# esquematico_placa.net
KiCad netlist of a schematic drawn in EAGLE
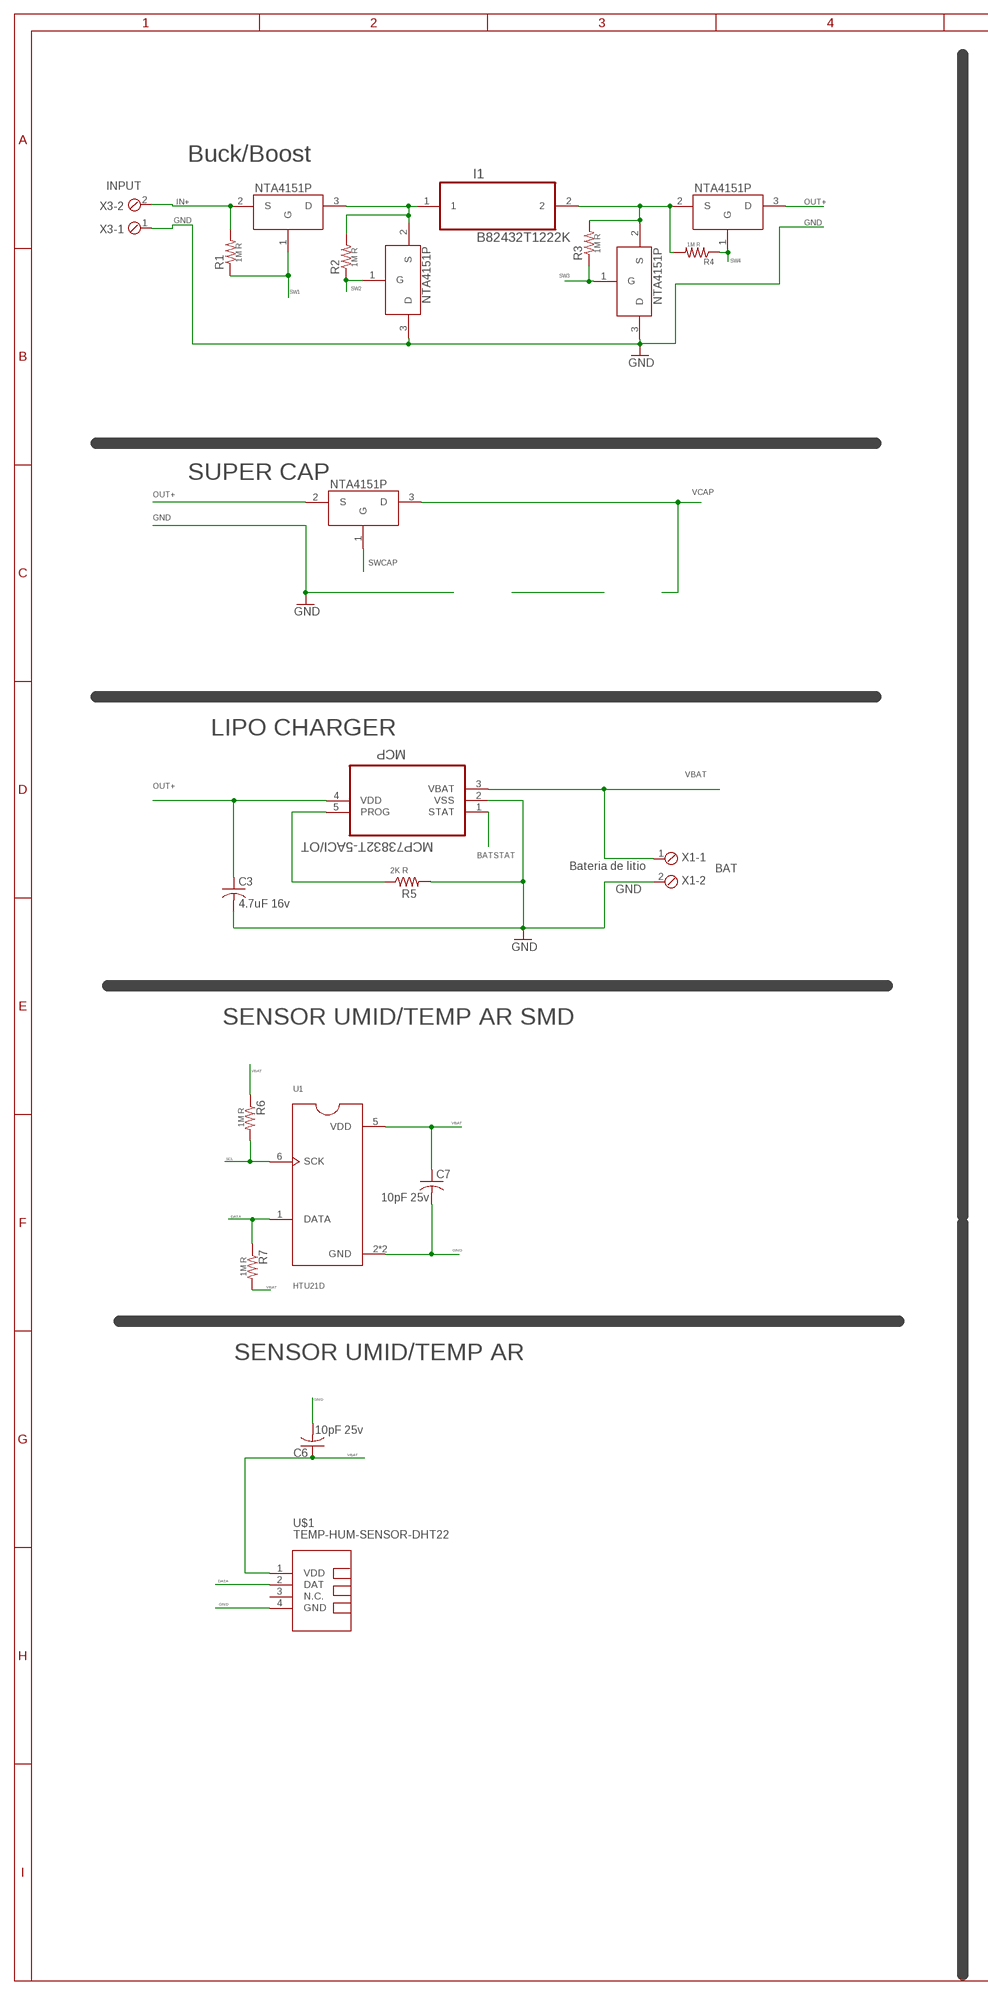
[diagram p0: schematic, sheet 1, part 1 of 2]
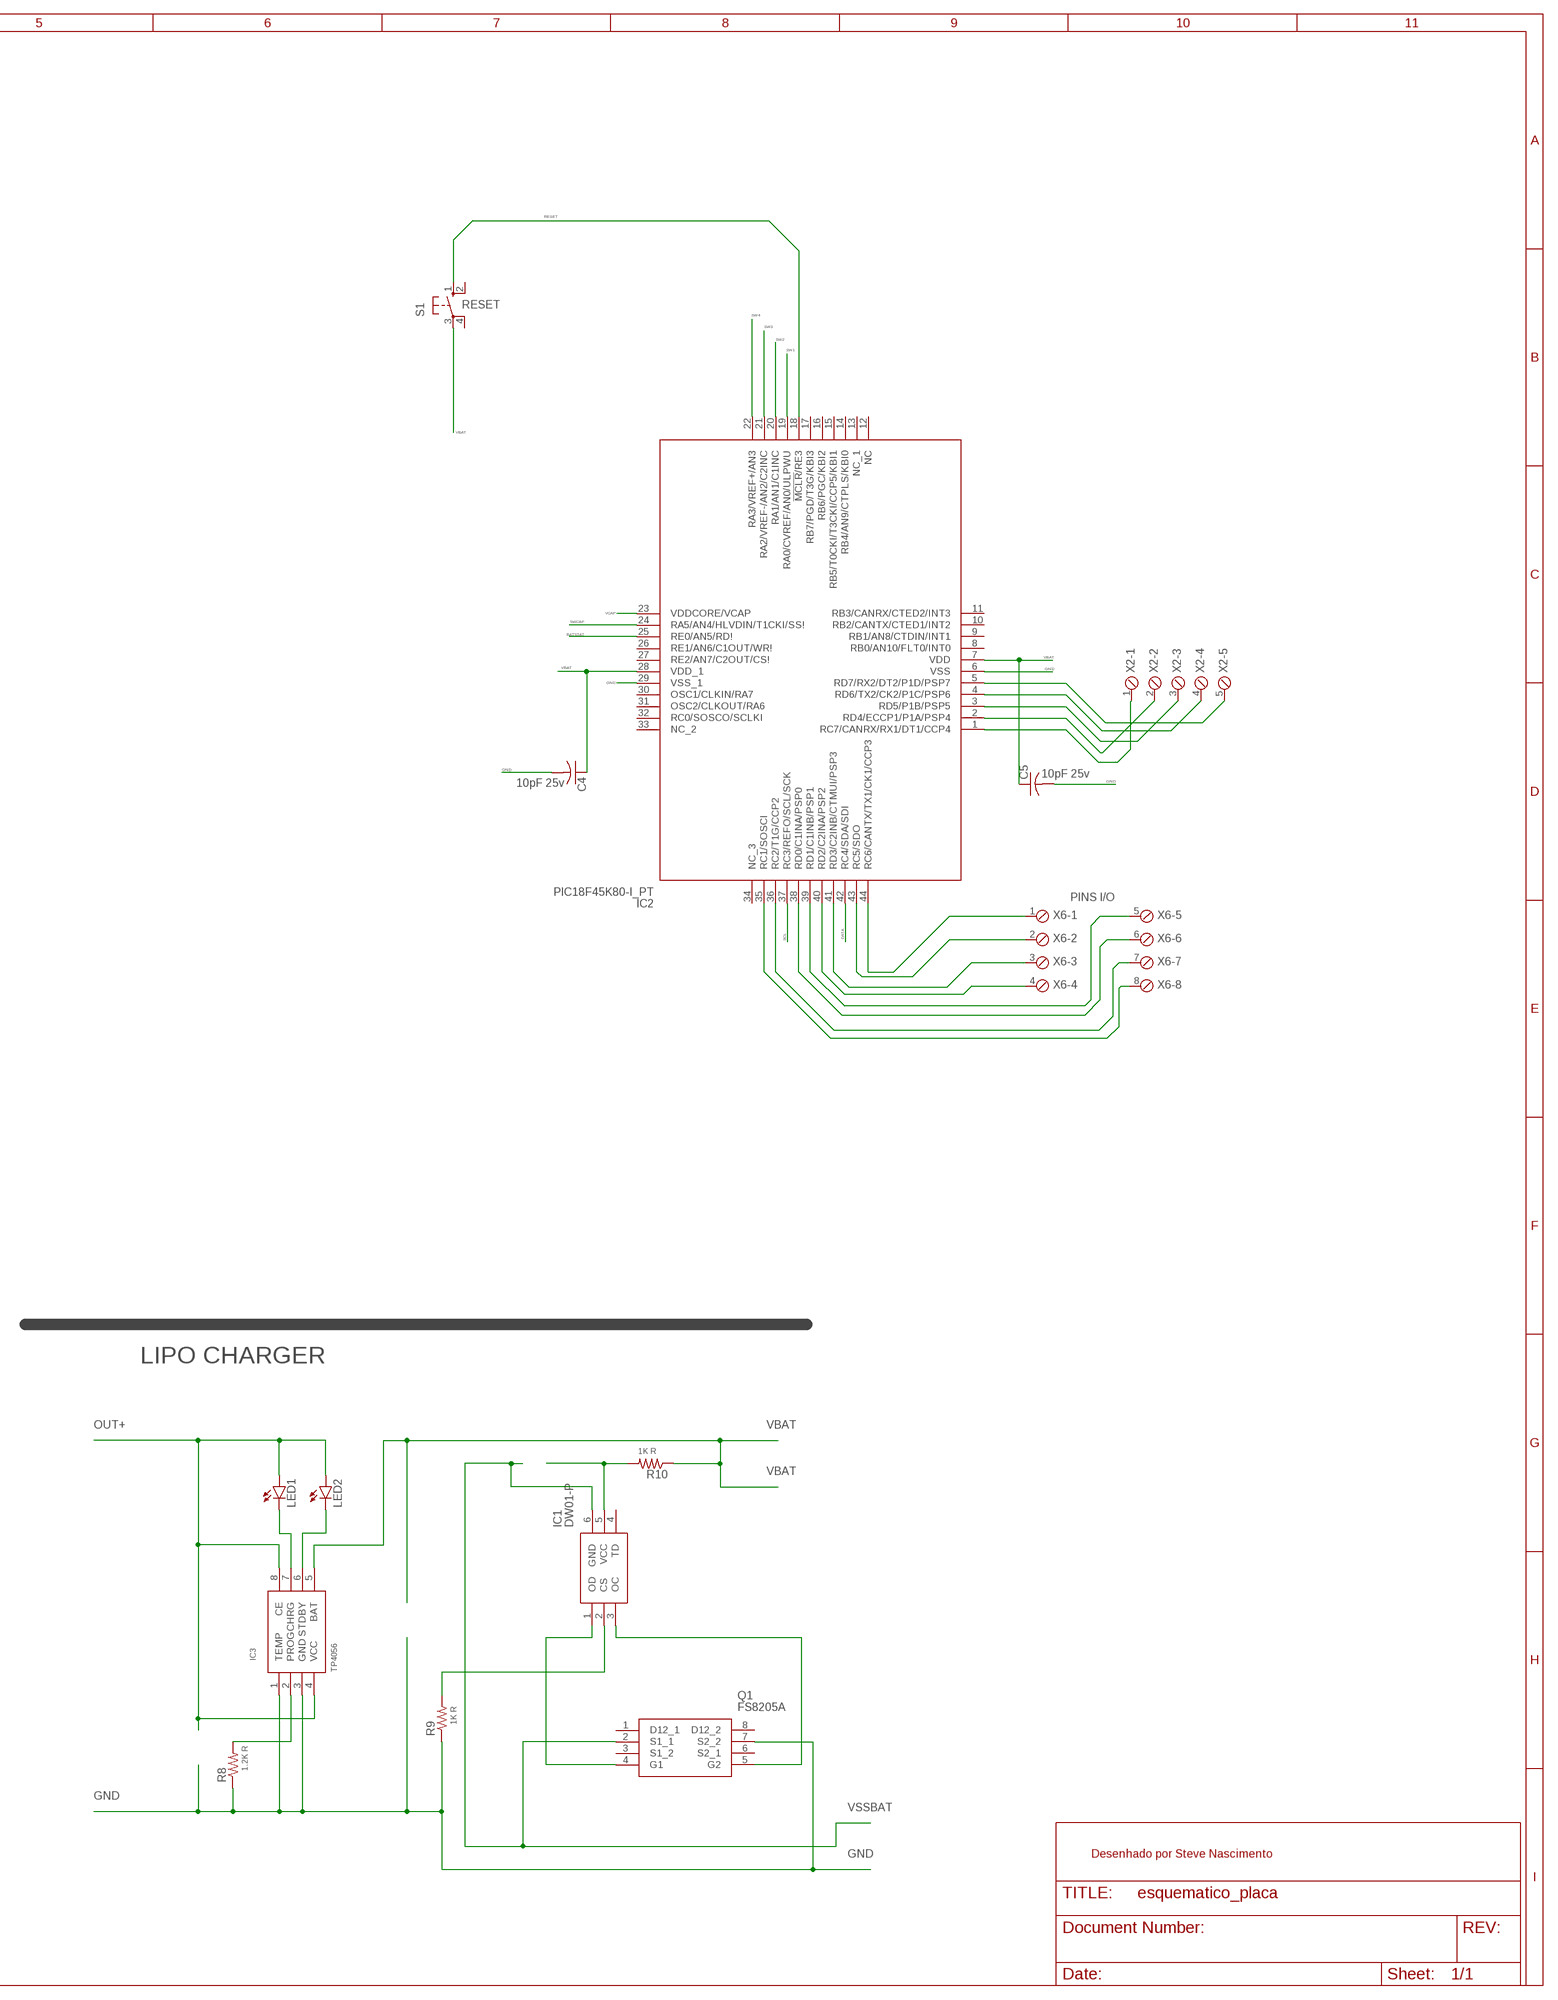
[diagram p1: schematic, sheet 1, part 2 of 2]

(export (version "E")
  (design (tool "Eeschema 10.0.6"))
  (components
    (comp (ref "C3")
      (value "4.7uF 16v")
      (footprint "eagle-import:C0805")
      (libsource (lib "eagle-import") (part "C-USC0805"))
    )
    (comp (ref "C4")
      (value "10pF 25v")
      (footprint "eagle-import:C0805")
      (libsource (lib "eagle-import") (part "C-USC0805"))
    )
    (comp (ref "C5")
      (value "10pF 25v")
      (footprint "eagle-import:C0805")
      (libsource (lib "eagle-import") (part "C-USC0805"))
    )
    (comp (ref "C6")
      (value "10pF 25v")
      (footprint "eagle-import:C0805")
      (libsource (lib "eagle-import") (part "C-USC0805"))
    )
    (comp (ref "C7")
      (value "10pF 25v")
      (footprint "eagle-import:C0805")
      (libsource (lib "eagle-import") (part "C-USC0805"))
    )
    (comp (ref "I1")
      (value "B82432T1222K")
      (footprint "eagle-import:INDC4532X340N")
      (fields (field (name "MF") "EPCOS"))
      (libsource (lib "eagle-import") (part "B82432T1222K"))
    )
    (comp (ref "IC1")
      (value "DW01-P")
      (footprint "eagle-import:SOT95P280X135-6N")
      (libsource (lib "eagle-import") (part "DW01-P"))
    )
    (comp (ref "IC2")
      (value "PIC18F45K80-I_PT")
      (footprint "eagle-import:QFP80P1200X1200X120-44N")
      (fields
        (field (name "MANUFACTURER_PART_NUMBER") "PIC18F45K80-I/PT")
        (field (name "MOUSER_PART_NUMBER") "579-PIC18F45K80-I/PT")
        (field (name "RS_PART_NUMBER") "8895477")
      )
      (libsource (lib "eagle-import") (part "PIC18F45K80-I_PT"))
    )
    (comp (ref "IC3")
      (value "TP4056")
      (footprint "eagle-import:SOP-8")
      (libsource (lib "eagle-import") (part "TP4056"))
    )
    (comp (ref "LED1")
      (value "LED5MM")
      (footprint "eagle-import:LED5MM")
      (libsource (lib "eagle-import") (part "LED5MM"))
    )
    (comp (ref "LED2")
      (value "LED5MM")
      (footprint "eagle-import:LED5MM")
      (libsource (lib "eagle-import") (part "LED5MM"))
    )
    (comp (ref "M1")
      (value "NTA4151P")
      (footprint "eagle-import:SOT50P160X90-3N")
      (libsource (lib "eagle-import") (part "NTA4151P"))
    )
    (comp (ref "M2")
      (value "NTA4151P")
      (footprint "eagle-import:SOT50P160X90-3N")
      (libsource (lib "eagle-import") (part "NTA4151P"))
    )
    (comp (ref "M3")
      (value "NTA4151P")
      (footprint "eagle-import:SOT50P160X90-3N")
      (libsource (lib "eagle-import") (part "NTA4151P"))
    )
    (comp (ref "M4")
      (value "NTA4151P")
      (footprint "eagle-import:SOT50P160X90-3N")
      (libsource (lib "eagle-import") (part "NTA4151P"))
    )
    (comp (ref "MCP")
      (value "MCP73832T-5ACI/OT")
      (footprint "eagle-import:SOT95P300X145-5N")
      (fields (field (name "MF") "Microchip"))
      (libsource (lib "eagle-import") (part "MCP73832T-5ACI/OT"))
    )
    (comp (ref "Q1")
      (value "FS8205A")
      (footprint "eagle-import:SOP65P640X120-8N")
      (libsource (lib "eagle-import") (part "FS8205A"))
    )
    (comp (ref "R1")
      (value "1M R")
      (footprint "eagle-import:RESC2012X65N")
      (fields
        (field (name "COMMENT") "5-1879509-5")
        (field (name "MF") "TE Connectivity")
        (field (name "MP") "CRGH0805F392R")
      )
      (libsource (lib "eagle-import") (part "CRGH0805F392R"))
    )
    (comp (ref "R2")
      (value "1M R")
      (footprint "eagle-import:RESC2012X65N")
      (fields
        (field (name "COMMENT") "5-1879509-5")
        (field (name "MF") "TE Connectivity")
        (field (name "MP") "CRGH0805F392R")
      )
      (libsource (lib "eagle-import") (part "CRGH0805F392R"))
    )
    (comp (ref "R3")
      (value "1M R")
      (footprint "eagle-import:RESC2012X65N")
      (fields
        (field (name "COMMENT") "5-1879509-5")
        (field (name "MF") "TE Connectivity")
        (field (name "MP") "CRGH0805F392R")
      )
      (libsource (lib "eagle-import") (part "CRGH0805F392R"))
    )
    (comp (ref "R4")
      (value "1M R")
      (footprint "eagle-import:RESC2012X65N")
      (fields
        (field (name "COMMENT") "5-1879509-5")
        (field (name "MF") "TE Connectivity")
        (field (name "MP") "CRGH0805F392R")
      )
      (libsource (lib "eagle-import") (part "CRGH0805F392R"))
    )
    (comp (ref "R5")
      (value "2K R")
      (footprint "eagle-import:RESC2012X65N")
      (fields
        (field (name "COMMENT") "5-1879509-5")
        (field (name "MF") "TE Connectivity")
        (field (name "MP") "CRGH0805F392R")
      )
      (libsource (lib "eagle-import") (part "CRGH0805F392R"))
    )
    (comp (ref "R6")
      (value "1M R")
      (footprint "eagle-import:RESC2012X65N")
      (fields
        (field (name "COMMENT") "5-1879509-5")
        (field (name "MF") "TE Connectivity")
        (field (name "MP") "CRGH0805F392R")
      )
      (libsource (lib "eagle-import") (part "CRGH0805F392R"))
    )
    (comp (ref "R7")
      (value "1M R")
      (footprint "eagle-import:RESC2012X65N")
      (fields
        (field (name "COMMENT") "5-1879509-5")
        (field (name "MF") "TE Connectivity")
        (field (name "MP") "CRGH0805F392R")
      )
      (libsource (lib "eagle-import") (part "CRGH0805F392R"))
    )
    (comp (ref "R8")
      (value "1.2K R")
      (footprint "eagle-import:RESC2012X65N")
      (fields
        (field (name "COMMENT") "5-1879509-5")
        (field (name "MF") "TE Connectivity")
        (field (name "MP") "CRGH0805F392R")
      )
      (libsource (lib "eagle-import") (part "CRGH0805F392R"))
    )
    (comp (ref "R9")
      (value "1K R")
      (footprint "eagle-import:RESC2012X65N")
      (fields
        (field (name "COMMENT") "5-1879509-5")
        (field (name "MF") "TE Connectivity")
        (field (name "MP") "CRGH0805F392R")
      )
      (libsource (lib "eagle-import") (part "CRGH0805F392R"))
    )
    (comp (ref "R10")
      (value "1K R")
      (footprint "eagle-import:RESC2012X65N")
      (fields
        (field (name "COMMENT") "5-1879509-5")
        (field (name "MF") "TE Connectivity")
        (field (name "MP") "CRGH0805F392R")
      )
      (libsource (lib "eagle-import") (part "CRGH0805F392R"))
    )
    (comp (ref "S1")
      (value "RESET")
      (footprint "eagle-import:B3F-10XX")
      (fields (field (name "MPN") "B3F-1000"))
      (libsource (lib "eagle-import") (part "10-XX"))
    )
    (comp (ref "SC")
      (value "NTA4151P")
      (footprint "eagle-import:SOT50P160X90-3N")
      (libsource (lib "eagle-import") (part "NTA4151P"))
    )
    (comp (ref "U$1")
      (value "TEMP-HUM-SENSOR-DHT22")
      (footprint "eagle-import:TEMP-HUM-SENSOR-DHT22")
      (libsource (lib "eagle-import") (part "TEMP-HUM-SENSOR-DHT22"))
    )
    (comp (ref "U1")
      (value "HTU21D")
      (footprint "eagle-import:QFN100P300X300X100-7N")
      (fields (field (name "COMMENT") "CAT-HSC0004") (field (name "MF") "TE Connectivity"))
      (libsource (lib "eagle-import") (part "HTU21D"))
    )
    (comp (ref "X1")
      (value "BAT")
      (footprint "eagle-import:2POL254")
      (libsource (lib "eagle-import") (part "MPT2"))
    )
    (comp (ref "X2")
      (value "MPT5")
      (footprint "eagle-import:5POL254")
      (libsource (lib "eagle-import") (part "MPT5"))
    )
    (comp (ref "X3")
      (value "INPUT")
      (footprint "eagle-import:2POL254")
      (libsource (lib "eagle-import") (part "MPT2"))
    )
    (comp (ref "X6")
      (value "PINS I/O")
      (footprint "eagle-import:8POL254")
      (libsource (lib "eagle-import") (part "MPT8"))
    )
  )
  (nets
    (net (code "1") (name "/BATSTAT") (class "Default")
      (node (ref "IC2") (pin "25") (pinfunction "RE0/AN5/RD~{}_25") (pintype "bidirectional"))
      (node (ref "MCP") (pin "1") (pinfunction "STAT_1") (pintype "input"))
    )
    (net (code "2") (name "/DATA") (class "Default")
      (node (ref "IC2") (pin "42") (pinfunction "RC4/SDA/SDI_42") (pintype "bidirectional"))
      (node (ref "R7") (pin "1") (pinfunction "1_1") (pintype "passive"))
      (node (ref "U$1") (pin "2") (pinfunction "DAT_2") (pintype "bidirectional"))
      (node (ref "U1") (pin "1") (pinfunction "DATA_1") (pintype "bidirectional"))
    )
    (net (code "3") (name "/IN+") (class "Default")
      (node (ref "M1") (pin "2") (pinfunction "S_2") (pintype "bidirectional"))
      (node (ref "R1") (pin "2") (pinfunction "2_2") (pintype "passive"))
      (node (ref "X3") (pin "2") (pinfunction "1_2") (pintype "passive"))
    )
    (net (code "4") (name "/OUT+") (class "Default")
      (node (ref "C3") (pin "1") (pinfunction "1_1") (pintype "passive"))
      (node (ref "IC3") (pin "4") (pinfunction "VCC_4") (pintype "bidirectional"))
      (node (ref "IC3") (pin "8") (pinfunction "CE_8") (pintype "bidirectional"))
      (node (ref "LED1") (pin "A") (pinfunction "A_A") (pintype "passive"))
      (node (ref "LED2") (pin "A") (pinfunction "A_A") (pintype "passive"))
      (node (ref "M4") (pin "3") (pinfunction "D_3") (pintype "bidirectional"))
      (node (ref "MCP") (pin "4") (pinfunction "VDD_4") (pintype "power_in"))
      (node (ref "SC") (pin "2") (pinfunction "S_2") (pintype "bidirectional"))
    )
    (net (code "5") (name "/RESET") (class "Default")
      (node (ref "IC2") (pin "18") (pinfunction "~{MCLR}/RE3_18") (pintype "bidirectional"))
      (node (ref "S1") (pin "1") (pinfunction "S_1") (pintype "passive"))
    )
    (net (code "6") (name "/SCL") (class "Default")
      (node (ref "IC2") (pin "37") (pinfunction "RC3/REFO/SCL/SCK_37") (pintype "input"))
      (node (ref "R6") (pin "2") (pinfunction "2_2") (pintype "passive"))
      (node (ref "U1") (pin "6") (pinfunction "SCK_6") (pintype "input"))
    )
    (net (code "7") (name "/SW1") (class "Default")
      (node (ref "IC2") (pin "19") (pinfunction "RA0/CVREF/AN0/ULPWU_19") (pintype "input"))
      (node (ref "M1") (pin "1") (pinfunction "G_1") (pintype "bidirectional"))
      (node (ref "R1") (pin "1") (pinfunction "1_1") (pintype "passive"))
    )
    (net (code "8") (name "/SW2") (class "Default")
      (node (ref "IC2") (pin "20") (pinfunction "RA1/AN1/C1INC_20") (pintype "input"))
      (node (ref "M2") (pin "1") (pinfunction "G_1") (pintype "bidirectional"))
      (node (ref "R2") (pin "1") (pinfunction "1_1") (pintype "passive"))
    )
    (net (code "9") (name "/SW3") (class "Default")
      (node (ref "IC2") (pin "21") (pinfunction "RA2/VREF-/AN2/C2INC_21") (pintype "input"))
      (node (ref "M3") (pin "1") (pinfunction "G_1") (pintype "bidirectional"))
      (node (ref "R3") (pin "1") (pinfunction "1_1") (pintype "passive"))
    )
    (net (code "10") (name "/SW4") (class "Default")
      (node (ref "IC2") (pin "22") (pinfunction "RA3/VREF+/AN3_22") (pintype "input"))
      (node (ref "M4") (pin "1") (pinfunction "G_1") (pintype "bidirectional"))
      (node (ref "R4") (pin "1") (pinfunction "1_1") (pintype "passive"))
    )
    (net (code "11") (name "/SWCAP") (class "Default")
      (node (ref "IC2") (pin "24") (pinfunction "RA5/AN4/HLVDIN/T1CKI/SS~{}_24") (pintype "input"))
      (node (ref "SC") (pin "1") (pinfunction "G_1") (pintype "bidirectional"))
    )
    (net (code "12") (name "/VBAT") (class "Default")
      (node (ref "C4") (pin "1") (pinfunction "1_1") (pintype "passive"))
      (node (ref "C5") (pin "1") (pinfunction "1_1") (pintype "passive"))
      (node (ref "C6") (pin "1") (pinfunction "1_1") (pintype "passive"))
      (node (ref "C7") (pin "1") (pinfunction "1_1") (pintype "passive"))
      (node (ref "IC2") (pin "28") (pinfunction "VDD_1_28") (pintype "power_in"))
      (node (ref "IC2") (pin "7") (pinfunction "VDD_7") (pintype "power_in"))
      (node (ref "IC3") (pin "5") (pinfunction "BAT_5") (pintype "bidirectional"))
      (node (ref "MCP") (pin "3") (pinfunction "VBAT_3") (pintype "input"))
      (node (ref "R10") (pin "1") (pinfunction "1_1") (pintype "passive"))
      (node (ref "R6") (pin "1") (pinfunction "1_1") (pintype "passive"))
      (node (ref "R7") (pin "2") (pinfunction "2_2") (pintype "passive"))
      (node (ref "S1") (pin "3") (pinfunction "P_3") (pintype "passive"))
      (node (ref "U$1") (pin "1") (pinfunction "VDD_1") (pintype "power_in"))
      (node (ref "U1") (pin "5") (pinfunction "VDD_5") (pintype "power_in"))
      (node (ref "X1") (pin "1") (pinfunction "1_1") (pintype "passive"))
    )
    (net (code "13") (name "/VCAP") (class "Default")
      (node (ref "IC2") (pin "23") (pinfunction "VDDCORE/VCAP_23") (pintype "power_in"))
      (node (ref "SC") (pin "3") (pinfunction "D_3") (pintype "bidirectional"))
    )
    (net (code "14") (name "/VSSBAT") (class "Default")
      (node (ref "IC1") (pin "6") (pinfunction "GND_6") (pintype "bidirectional"))
      (node (ref "Q1") (pin "2") (pinfunction "S1_1_2") (pintype "bidirectional"))
    )
    (net (code "15") (name "GND") (class "Default")
      (node (ref "C3") (pin "2") (pinfunction "2_2") (pintype "passive"))
      (node (ref "C4") (pin "2") (pinfunction "2_2") (pintype "passive"))
      (node (ref "C5") (pin "2") (pinfunction "2_2") (pintype "passive"))
      (node (ref "C6") (pin "2") (pinfunction "2_2") (pintype "passive"))
      (node (ref "C7") (pin "2") (pinfunction "2_2") (pintype "passive"))
      (node (ref "IC2") (pin "29") (pinfunction "VSS_1_29") (pintype "power_in"))
      (node (ref "IC2") (pin "6") (pinfunction "VSS_6") (pintype "power_in"))
      (node (ref "IC3") (pin "1") (pinfunction "TEMP_1") (pintype "bidirectional"))
      (node (ref "IC3") (pin "3") (pinfunction "GND_3") (pintype "bidirectional"))
      (node (ref "M2") (pin "3") (pinfunction "D_3") (pintype "bidirectional"))
      (node (ref "M3") (pin "3") (pinfunction "D_3") (pintype "bidirectional"))
      (node (ref "MCP") (pin "2") (pinfunction "VSS_2") (pintype "passive"))
      (node (ref "Q1") (pin "7") (pinfunction "S2_2_7") (pintype "bidirectional"))
      (node (ref "R5") (pin "2") (pinfunction "2_2") (pintype "passive"))
      (node (ref "R8") (pin "1") (pinfunction "1_1") (pintype "passive"))
      (node (ref "R9") (pin "1") (pinfunction "1_1") (pintype "passive"))
      (node (ref "U$1") (pin "4") (pinfunction "GND_4") (pintype "power_in"))
      (node (ref "U1") (pin "2") (pinfunction "GND_2") (pintype "passive"))
      (node (ref "U1") (pin "PAD") (pinfunction "GND_PAD") (pintype "passive"))
      (node (ref "X1") (pin "2") (pinfunction "1_2") (pintype "passive"))
      (node (ref "X3") (pin "1") (pinfunction "1_1") (pintype "passive"))
    )
    (net (code "16") (name "Net-(IC1-CS)") (class "Default")
      (node (ref "IC1") (pin "2") (pinfunction "CS_2") (pintype "bidirectional"))
      (node (ref "R9") (pin "2") (pinfunction "2_2") (pintype "passive"))
    )
    (net (code "17") (name "Net-(IC1-OC)") (class "Default")
      (node (ref "IC1") (pin "3") (pinfunction "OC_3") (pintype "bidirectional"))
      (node (ref "Q1") (pin "5") (pinfunction "G2_5") (pintype "bidirectional"))
    )
    (net (code "18") (name "Net-(IC1-OD)") (class "Default")
      (node (ref "IC1") (pin "1") (pinfunction "OD_1") (pintype "bidirectional"))
      (node (ref "Q1") (pin "4") (pinfunction "G1_4") (pintype "bidirectional"))
    )
    (net (code "19") (name "Net-(IC1-VCC)") (class "Default")
      (node (ref "IC1") (pin "5") (pinfunction "VCC_5") (pintype "bidirectional"))
      (node (ref "R10") (pin "2") (pinfunction "2_2") (pintype "passive"))
    )
    (net (code "20") (name "Net-(IC2-RC1{slash}SOSCI)") (class "Default")
      (node (ref "IC2") (pin "35") (pinfunction "RC1/SOSCI_35") (pintype "bidirectional"))
      (node (ref "X6") (pin "8") (pinfunction "1_8") (pintype "passive"))
    )
    (net (code "21") (name "Net-(IC2-RC2{slash}T1G{slash}CCP2)") (class "Default")
      (node (ref "IC2") (pin "36") (pinfunction "RC2/T1G/CCP2_36") (pintype "bidirectional"))
      (node (ref "X6") (pin "7") (pinfunction "1_7") (pintype "passive"))
    )
    (net (code "22") (name "Net-(IC2-RC5{slash}SDO)") (class "Default")
      (node (ref "IC2") (pin "43") (pinfunction "RC5/SDO_43") (pintype "bidirectional"))
      (node (ref "X6") (pin "2") (pinfunction "1_2") (pintype "passive"))
    )
    (net (code "23") (name "Net-(IC2-RC6{slash}CANTX{slash}TX1{slash}CK1{slash}CCP3)") (class "Default")
      (node (ref "IC2") (pin "44") (pinfunction "RC6/CANTX/TX1/CK1/CCP3_44") (pintype "bidirectional"))
      (node (ref "X6") (pin "1") (pinfunction "1_1") (pintype "passive"))
    )
    (net (code "24") (name "Net-(IC2-RC7{slash}CANRX{slash}RX1{slash}DT1{slash}CCP4)") (class "Default")
      (node (ref "IC2") (pin "1") (pinfunction "RC7/CANRX/RX1/DT1/CCP4_1") (pintype "bidirectional"))
      (node (ref "X2") (pin "1") (pinfunction "1_1") (pintype "passive"))
    )
    (net (code "25") (name "Net-(IC2-RD0{slash}C1INA{slash}PSP0)") (class "Default")
      (node (ref "IC2") (pin "38") (pinfunction "RD0/C1INA/PSP0_38") (pintype "input"))
      (node (ref "X6") (pin "6") (pinfunction "1_6") (pintype "passive"))
    )
    (net (code "26") (name "Net-(IC2-RD1{slash}C1INB{slash}PSP1)") (class "Default")
      (node (ref "IC2") (pin "39") (pinfunction "RD1/C1INB/PSP1_39") (pintype "input"))
      (node (ref "X6") (pin "5") (pinfunction "1_5") (pintype "passive"))
    )
    (net (code "27") (name "Net-(IC2-RD2{slash}C2INA{slash}PSP2)") (class "Default")
      (node (ref "IC2") (pin "40") (pinfunction "RD2/C2INA/PSP2_40") (pintype "input"))
      (node (ref "X6") (pin "4") (pinfunction "1_4") (pintype "passive"))
    )
    (net (code "28") (name "Net-(IC2-RD3{slash}C2INB{slash}CTMUI{slash}PSP3)") (class "Default")
      (node (ref "IC2") (pin "41") (pinfunction "RD3/C2INB/CTMUI/PSP3_41") (pintype "input"))
      (node (ref "X6") (pin "3") (pinfunction "1_3") (pintype "passive"))
    )
    (net (code "29") (name "Net-(IC2-RD4{slash}ECCP1{slash}P1A{slash}PSP4)") (class "Default")
      (node (ref "IC2") (pin "2") (pinfunction "RD4/ECCP1/P1A/PSP4_2") (pintype "bidirectional"))
      (node (ref "X2") (pin "2") (pinfunction "1_2") (pintype "passive"))
    )
    (net (code "30") (name "Net-(IC2-RD5{slash}P1B{slash}PSP5)") (class "Default")
      (node (ref "IC2") (pin "3") (pinfunction "RD5/P1B/PSP5_3") (pintype "bidirectional"))
      (node (ref "X2") (pin "3") (pinfunction "1_3") (pintype "passive"))
    )
    (net (code "31") (name "Net-(IC2-RD6{slash}TX2{slash}CK2{slash}P1C{slash}PSP6)") (class "Default")
      (node (ref "IC2") (pin "4") (pinfunction "RD6/TX2/CK2/P1C/PSP6_4") (pintype "bidirectional"))
      (node (ref "X2") (pin "4") (pinfunction "1_4") (pintype "passive"))
    )
    (net (code "32") (name "Net-(IC2-RD7{slash}RX2{slash}DT2{slash}P1D{slash}PSP7)") (class "Default")
      (node (ref "IC2") (pin "5") (pinfunction "RD7/RX2/DT2/P1D/PSP7_5") (pintype "bidirectional"))
      (node (ref "X2") (pin "5") (pinfunction "1_5") (pintype "passive"))
    )
    (net (code "33") (name "Net-(IC3-CHRG)") (class "Default")
      (node (ref "IC3") (pin "7") (pinfunction "CHRG_7") (pintype "bidirectional"))
      (node (ref "LED1") (pin "K") (pinfunction "C_K") (pintype "passive"))
    )
    (net (code "34") (name "Net-(IC3-PROG)") (class "Default")
      (node (ref "IC3") (pin "2") (pinfunction "PROG_2") (pintype "bidirectional"))
      (node (ref "R8") (pin "2") (pinfunction "2_2") (pintype "passive"))
    )
    (net (code "35") (name "Net-(IC3-STDBY)") (class "Default")
      (node (ref "IC3") (pin "6") (pinfunction "STDBY_6") (pintype "bidirectional"))
      (node (ref "LED2") (pin "K") (pinfunction "C_K") (pintype "passive"))
    )
    (net (code "36") (name "Net-(M1-D)") (class "Default")
      (node (ref "I1") (pin "1") (pinfunction "1_1") (pintype "passive"))
      (node (ref "M1") (pin "3") (pinfunction "D_3") (pintype "bidirectional"))
      (node (ref "M2") (pin "2") (pinfunction "S_2") (pintype "bidirectional"))
      (node (ref "R2") (pin "2") (pinfunction "2_2") (pintype "passive"))
    )
    (net (code "37") (name "Net-(M3-S)") (class "Default")
      (node (ref "I1") (pin "2") (pinfunction "2_2") (pintype "passive"))
      (node (ref "M3") (pin "2") (pinfunction "S_2") (pintype "bidirectional"))
      (node (ref "M4") (pin "2") (pinfunction "S_2") (pintype "bidirectional"))
      (node (ref "R3") (pin "2") (pinfunction "2_2") (pintype "passive"))
      (node (ref "R4") (pin "2") (pinfunction "2_2") (pintype "passive"))
    )
    (net (code "38") (name "Net-(MCP-PROG)") (class "Default")
      (node (ref "MCP") (pin "5") (pinfunction "PROG_5") (pintype "input"))
      (node (ref "R5") (pin "1") (pinfunction "1_1") (pintype "passive"))
    )
    (net (code "39") (name "unconnected-(IC1-TD-Pad4)") (class "Default")
      (node (ref "IC1") (pin "4") (pinfunction "TD_4") (pintype "bidirectional"))
    )
    (net (code "40") (name "unconnected-(IC2-NC-Pad12)") (class "Default")
      (node (ref "IC2") (pin "12") (pinfunction "NC_12") (pintype "no_connect"))
    )
    (net (code "41") (name "unconnected-(IC2-NC_1-Pad13)") (class "Default")
      (node (ref "IC2") (pin "13") (pinfunction "NC_1_13") (pintype "bidirectional"))
    )
    (net (code "42") (name "unconnected-(IC2-NC_2-Pad33)") (class "Default")
      (node (ref "IC2") (pin "33") (pinfunction "NC_2_33") (pintype "bidirectional"))
    )
    (net (code "43") (name "unconnected-(IC2-NC_3-Pad34)") (class "Default")
      (node (ref "IC2") (pin "34") (pinfunction "NC_3_34") (pintype "bidirectional"))
    )
    (net (code "44") (name "unconnected-(IC2-OSC1{slash}CLKIN{slash}RA7-Pad30)") (class "Default")
      (node (ref "IC2") (pin "30") (pinfunction "OSC1/CLKIN/RA7_30") (pintype "input"))
    )
    (net (code "45") (name "unconnected-(IC2-OSC2{slash}CLKOUT{slash}RA6-Pad31)") (class "Default")
      (node (ref "IC2") (pin "31") (pinfunction "OSC2/CLKOUT/RA6_31") (pintype "output"))
    )
    (net (code "46") (name "unconnected-(IC2-RB0{slash}AN10{slash}FLT0{slash}INT0-Pad8)") (class "Default")
      (node (ref "IC2") (pin "8") (pinfunction "RB0/AN10/FLT0/INT0_8") (pintype "input"))
    )
    (net (code "47") (name "unconnected-(IC2-RB1{slash}AN8{slash}CTDIN{slash}INT1-Pad9)") (class "Default")
      (node (ref "IC2") (pin "9") (pinfunction "RB1/AN8/CTDIN/INT1_9") (pintype "input"))
    )
    (net (code "48") (name "unconnected-(IC2-RB2{slash}CANTX{slash}CTED1{slash}INT2-Pad10)") (class "Default")
      (node (ref "IC2") (pin "10") (pinfunction "RB2/CANTX/CTED1/INT2_10") (pintype "input"))
    )
    (net (code "49") (name "unconnected-(IC2-RB3{slash}CANRX{slash}CTED2{slash}INT3-Pad11)") (class "Default")
      (node (ref "IC2") (pin "11") (pinfunction "RB3/CANRX/CTED2/INT3_11") (pintype "input"))
    )
    (net (code "50") (name "unconnected-(IC2-RB4{slash}AN9{slash}CTPLS{slash}KBI0-Pad14)") (class "Default")
      (node (ref "IC2") (pin "14") (pinfunction "RB4/AN9/CTPLS/KBI0_14") (pintype "bidirectional"))
    )
    (net (code "51") (name "unconnected-(IC2-RB5{slash}T0CKI{slash}T3CKI{slash}CCP5{slash}KBI1-Pad15)") (class "Default")
      (node (ref "IC2") (pin "15") (pinfunction "RB5/T0CKI/T3CKI/CCP5/KBI1_15") (pintype "bidirectional"))
    )
    (net (code "52") (name "unconnected-(IC2-RB6{slash}PGC{slash}KBI2-Pad16)") (class "Default")
      (node (ref "IC2") (pin "16") (pinfunction "RB6/PGC/KBI2_16") (pintype "bidirectional"))
    )
    (net (code "53") (name "unconnected-(IC2-RB7{slash}PGD{slash}T3G{slash}KBI3-Pad17)") (class "Default")
      (node (ref "IC2") (pin "17") (pinfunction "RB7/PGD/T3G/KBI3_17") (pintype "bidirectional"))
    )
    (net (code "54") (name "unconnected-(IC2-RC0{slash}SOSCO{slash}SCLKI-Pad32)") (class "Default")
      (node (ref "IC2") (pin "32") (pinfunction "RC0/SOSCO/SCLKI_32") (pintype "input"))
    )
    (net (code "55") (name "unconnected-(IC2-RE1{slash}AN6{slash}C1OUT{slash}WR~{}-Pad26)") (class "Default")
      (node (ref "IC2") (pin "26") (pinfunction "RE1/AN6/C1OUT/WR~{}_26") (pintype "output"))
    )
    (net (code "56") (name "unconnected-(IC2-RE2{slash}AN7{slash}C2OUT{slash}CS~{}-Pad27)") (class "Default")
      (node (ref "IC2") (pin "27") (pinfunction "RE2/AN7/C2OUT/CS~{}_27") (pintype "output"))
    )
    (net (code "57") (name "unconnected-(Q1-D12_1-Pad1)") (class "Default")
      (node (ref "Q1") (pin "1") (pinfunction "D12_1_1") (pintype "bidirectional"))
    )
    (net (code "58") (name "unconnected-(Q1-D12_2-Pad8)") (class "Default")
      (node (ref "Q1") (pin "8") (pinfunction "D12_2_8") (pintype "bidirectional"))
    )
    (net (code "59") (name "unconnected-(Q1-S1_2-Pad3)") (class "Default")
      (node (ref "Q1") (pin "3") (pinfunction "S1_2_3") (pintype "bidirectional"))
    )
    (net (code "60") (name "unconnected-(Q1-S2_1-Pad6)") (class "Default")
      (node (ref "Q1") (pin "6") (pinfunction "S2_1_6") (pintype "bidirectional"))
    )
    (net (code "61") (name "unconnected-(S1-P1-Pad4)") (class "Default")
      (node (ref "S1") (pin "4") (pinfunction "P1_4") (pintype "passive"))
    )
    (net (code "62") (name "unconnected-(S1-S1-Pad2)") (class "Default")
      (node (ref "S1") (pin "2") (pinfunction "S1_2") (pintype "passive"))
    )
    (net (code "63") (name "unconnected-(U$1-N.C.-Pad3)") (class "Default")
      (node (ref "U$1") (pin "3") (pinfunction "N.C._3") (pintype "passive"))
    )
  )
)
